# Hexbot_Stm32.net
KiCad netlist of a schematic drawn in Altium Designer
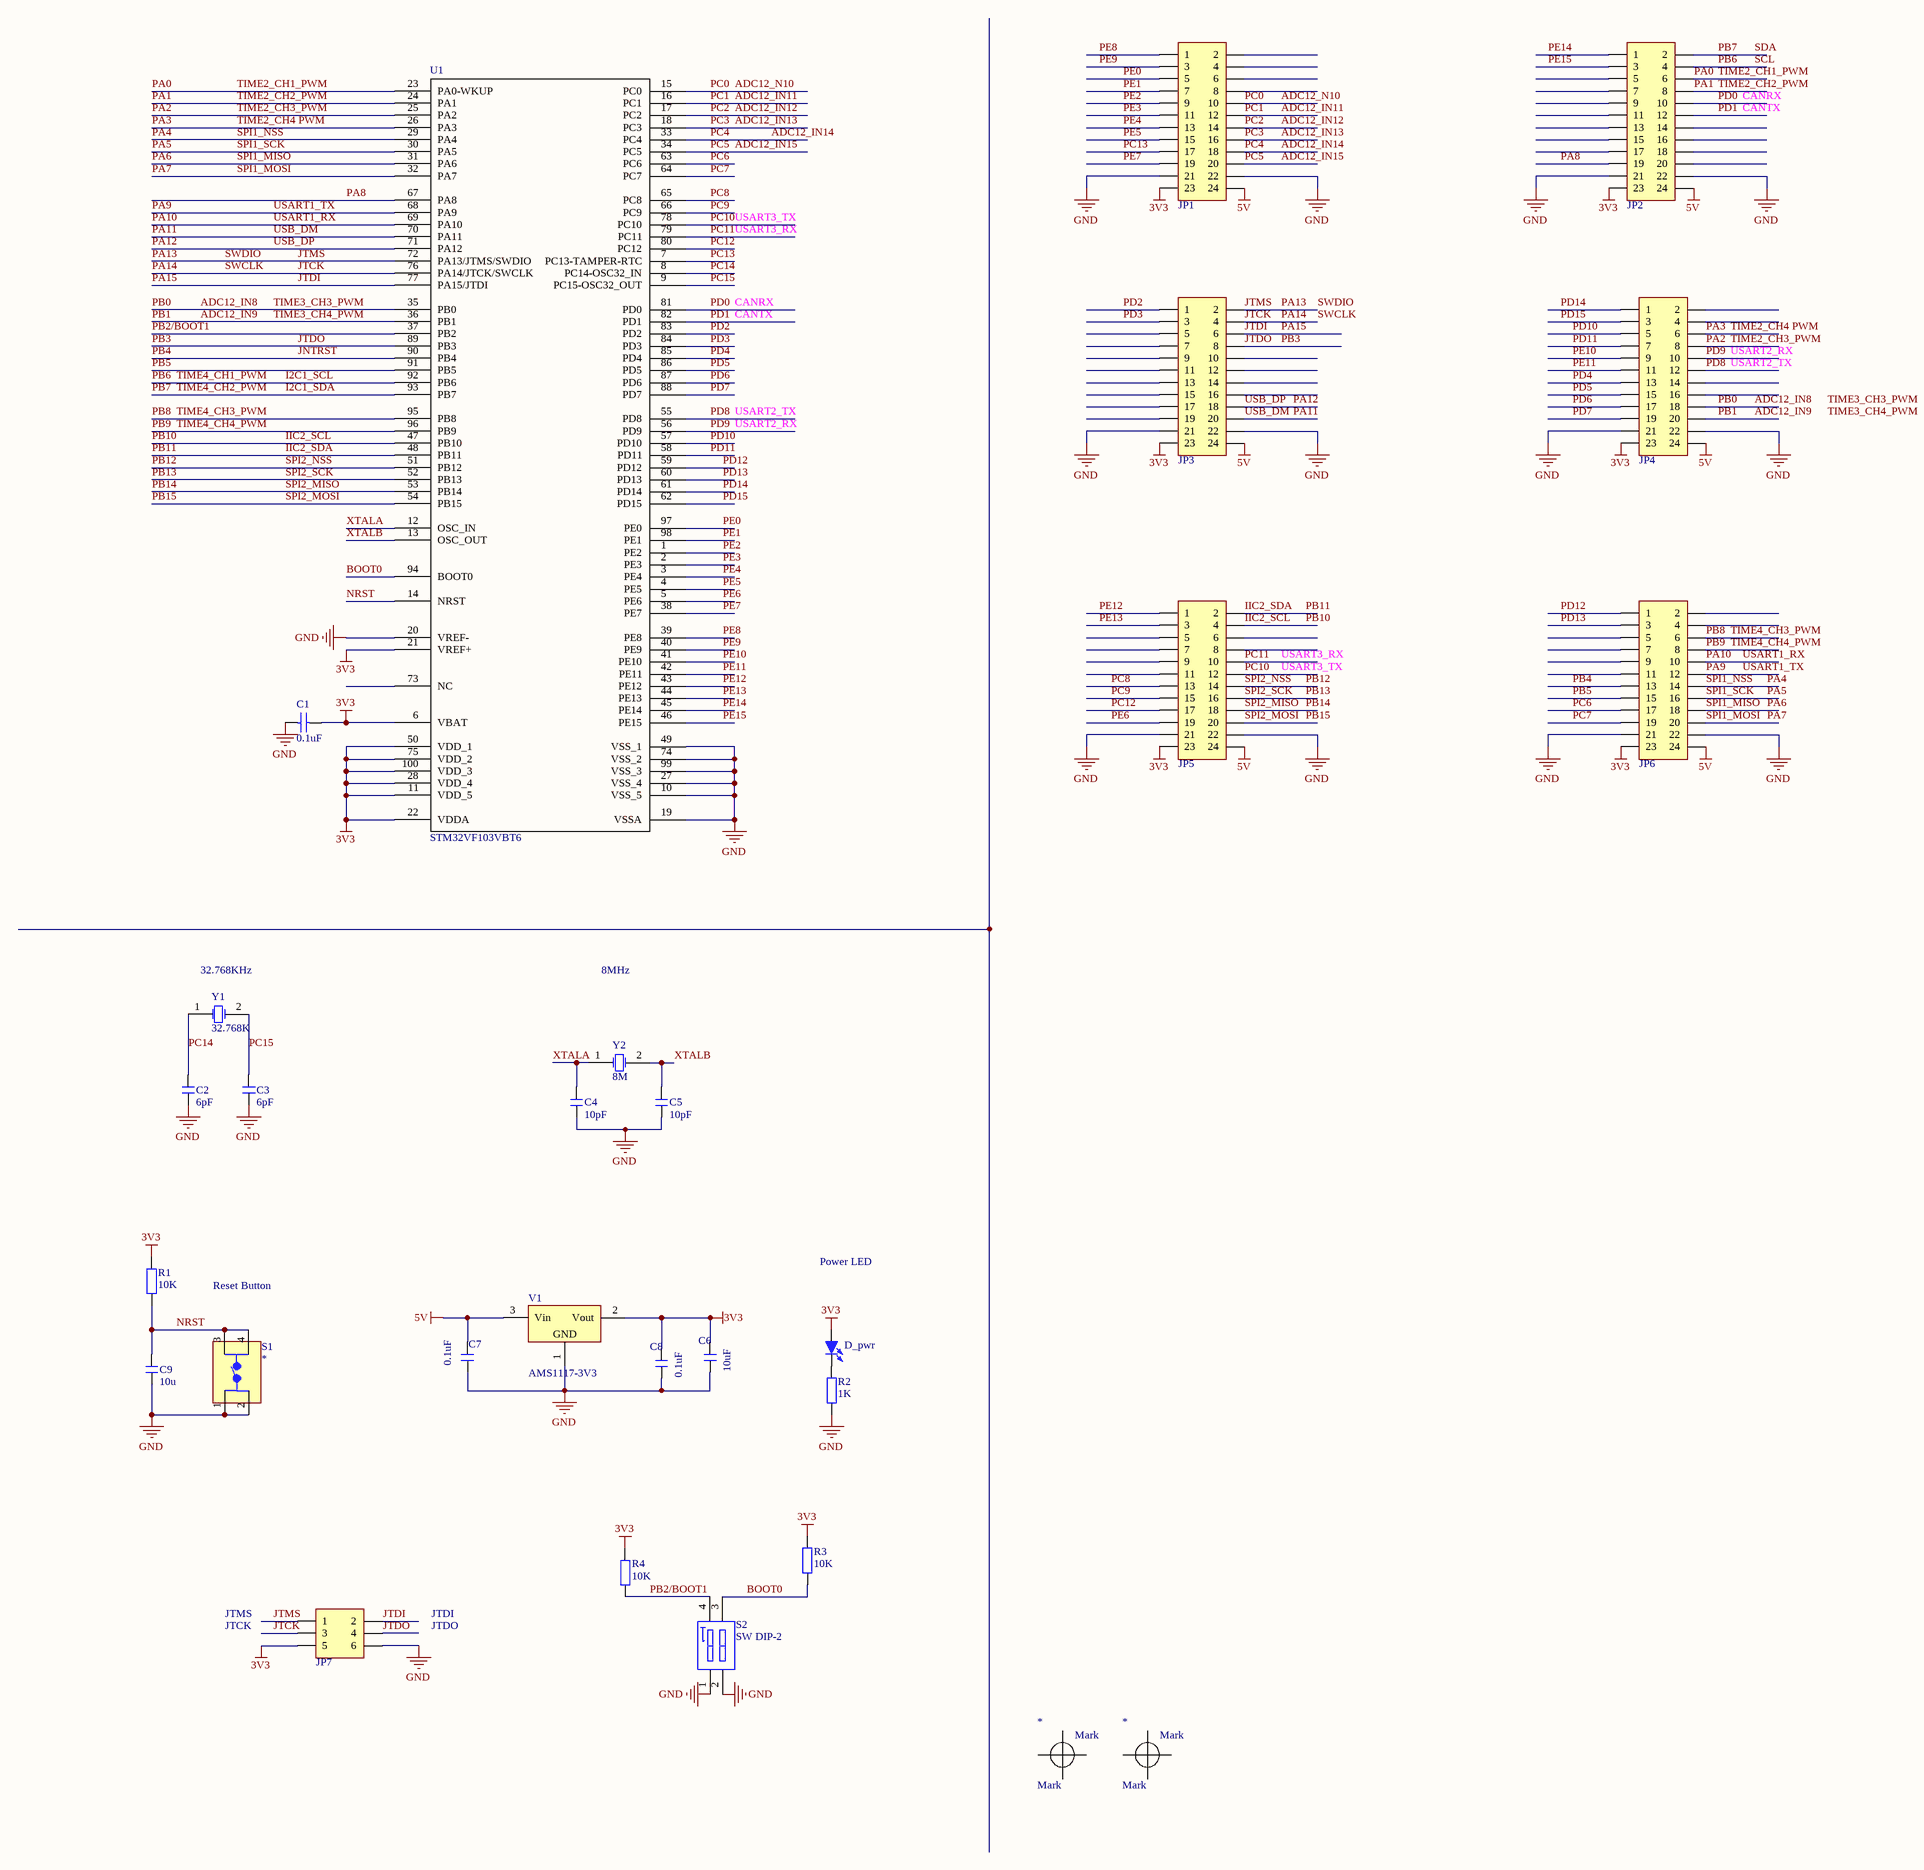
[diagram p0: Hexbot_Stm32.SchDoc]

(export (version "E")
  (design (tool "Eeschema 10.0.6"))
  (components
    (comp (ref "C1")
      (value "0.1uF")
      (footprint "1608[0603]")
      (description "Capacitor (Semiconductor SIM Model)")
      (fields (field (name "Comment") "Cap Semi") (field (name "PUBLISHER") "Altium Limited"))
      (libsource (lib "Miscellaneous Devices") (part "Cap Semi"))
    )
    (comp (ref "C2")
      (value "6pF")
      (footprint "C 0603_L")
      (description "贴片电容")
      (libsource (lib "0.1 - 电阻-电容-电感") (part "C"))
    )
    (comp (ref "C3")
      (value "6pF")
      (footprint "C 0603_L")
      (description "贴片电容")
      (libsource (lib "0.1 - 电阻-电容-电感") (part "C"))
    )
    (comp (ref "C4")
      (value "10pF")
      (footprint "C 0603_L")
      (description "贴片电容")
      (libsource (lib "0.1 - 电阻-电容-电感") (part "C"))
    )
    (comp (ref "C5")
      (value "10pF")
      (footprint "C 0603_L")
      (description "贴片电容")
      (libsource (lib "0.1 - 电阻-电容-电感") (part "C"))
    )
    (comp (ref "C6")
      (value "10uF")
      (footprint "C 0603_L")
      (description "贴片电容")
      (libsource (lib "0.1 - 电阻-电容-电感") (part "C"))
    )
    (comp (ref "C7")
      (value "0.1uF")
      (footprint "C 0603_L")
      (description "贴片电容")
      (libsource (lib "0.1 - 电阻-电容-电感") (part "C"))
    )
    (comp (ref "C8")
      (value "0.1uF")
      (footprint "C 0603_L")
      (description "贴片电容")
      (libsource (lib "0.1 - 电阻-电容-电感") (part "C"))
    )
    (comp (ref "C9")
      (value "10u")
      (footprint "C 0603_L")
      (description "贴片电容")
      (libsource (lib "0.1 - 电阻-电容-电感") (part "C"))
    )
    (comp (ref "D_pwr")
      (value "~")
      (footprint "LED 0603R")
      (description "贴片LED")
      (fields (field (name "版权归属") "封装库来自淘宝 ID：黄晶宝石"))
      (libsource (lib "0.3 - LED发光二极管") (part "LED-SMD"))
    )
    (comp (ref "JP1")
      (value "Header 2X11")
      (footprint "HDR2.54-WI-2x12P")
      (description "12*2P接插件")
      (fields (field (name "版权归属") "封装库来自淘宝卖家 ID：黄晶宝石"))
      (libsource (lib "5.4 - 接插件-脚距2.54 (100mil) ") (part "Header 12X2"))
    )
    (comp (ref "JP2")
      (value "Header 2X11")
      (footprint "HDR2.54-WI-2x12P")
      (description "12*2P接插件")
      (fields (field (name "版权归属") "封装库来自淘宝卖家 ID：黄晶宝石"))
      (libsource (lib "5.4 - 接插件-脚距2.54 (100mil) ") (part "Header 12X2"))
    )
    (comp (ref "JP3")
      (value "Header 2X11")
      (footprint "HDR2.54-WI-2x12P")
      (description "12*2P接插件")
      (fields (field (name "版权归属") "封装库来自淘宝卖家 ID：黄晶宝石"))
      (libsource (lib "5.4 - 接插件-脚距2.54 (100mil) ") (part "Header 12X2"))
    )
    (comp (ref "JP4")
      (value "Header 2X11")
      (footprint "HDR2.54-WI-2x12P")
      (description "12*2P接插件")
      (fields (field (name "版权归属") "封装库来自淘宝卖家 ID：黄晶宝石"))
      (libsource (lib "5.4 - 接插件-脚距2.54 (100mil) ") (part "Header 12X2"))
    )
    (comp (ref "JP5")
      (value "Header 2X11")
      (footprint "HDR2.54-WI-2x12P")
      (description "12*2P接插件")
      (fields (field (name "版权归属") "封装库来自淘宝卖家 ID：黄晶宝石"))
      (libsource (lib "5.4 - 接插件-脚距2.54 (100mil) ") (part "Header 12X2"))
    )
    (comp (ref "JP6")
      (value "Header 2X11")
      (footprint "HDR2.54-WI-2x12P")
      (description "12*2P接插件")
      (fields (field (name "版权归属") "封装库来自淘宝卖家 ID：黄晶宝石"))
      (libsource (lib "5.4 - 接插件-脚距2.54 (100mil) ") (part "Header 12X2"))
    )
    (comp (ref "JP7")
      (value "Header3X2")
      (footprint "HDR2.54-LI-2x3P")
      (description "3*2P接插件")
      (fields (field (name "版权归属") "封装库来自淘宝 ID：黄晶宝石"))
      (libsource (lib "5.4 - 接插件-脚距2.54 (100mil) ") (part "Header 3X2"))
    )
    (comp (ref "R1")
      (value "10K")
      (footprint "R 0603_L")
      (description "贴片电阻")
      (fields (field (name "版权归属") "来自淘宝 ID：黄晶宝石"))
      (libsource (lib "0.1 - 电阻-电容-电感") (part "R"))
    )
    (comp (ref "R2")
      (value "1K")
      (footprint "R 0603_L")
      (description "贴片电阻")
      (fields (field (name "版权归属") "来自淘宝 ID：黄晶宝石"))
      (libsource (lib "0.1 - 电阻-电容-电感") (part "R"))
    )
    (comp (ref "R3")
      (value "10K")
      (footprint "R 0603_L")
      (description "贴片电阻")
      (fields (field (name "版权归属") "来自淘宝 ID：黄晶宝石"))
      (libsource (lib "0.1 - 电阻-电容-电感") (part "R"))
    )
    (comp (ref "R4")
      (value "10K")
      (footprint "R 0603_L")
      (description "贴片电阻")
      (fields (field (name "版权归属") "来自淘宝 ID：黄晶宝石"))
      (libsource (lib "0.1 - 电阻-电容-电感") (part "R"))
    )
    (comp (ref "S1")
      (value "4-1437565-1")
      (footprint "BUTTON")
      (description "Tactile Switch SPST-NO Top Actuated Surface Mount")
      (fields
        (field (name "MP") "FSM4JSMA")
        (field (name "MF") "TE Connectivity")
        (field (name "COMMENT_1") "*")
      )
      (libsource (lib "hexbot_main") (part "FSM4JSMA"))
    )
    (comp (ref "S2")
      (value "SW DIP-2")
      (footprint "SMD-2")
      (description "DIP Switch, 2 Position, SPST")
      (fields (field (name "PUBLISHER") "Altium Limited"))
      (libsource (lib "hexbot_main") (part "SW DIP-2"))
    )
    (comp (ref "U1")
      (value "STM32VF103VBT6")
      (footprint "GDF103C8T6QFN100")
      (libsource (lib "GD32VF103VBT6") (part "GD32VF103VBT6"))
    )
    (comp (ref "V1")
      (value "AMS1117-3V3")
      (footprint "SOT223_L")
      (description "三端稳压芯片")
      (libsource (lib "1.1 - 电源类芯片") (part "AMS1117"))
    )
    (comp (ref "Y1")
      (value "32.768K")
      (footprint "32.768KHZ")
      (description "Crystal Oscillator")
      (fields (field (name "PUBLISHER") "Altium Limited"))
      (libsource (lib "hexbot_main") (part "XTAL_1"))
    )
    (comp (ref "Y2")
      (value "8M")
      (footprint "8M")
      (description "Crystal Oscillator")
      (fields (field (name "PUBLISHER") "Altium Limited"))
      (libsource (lib "hexbot_main") (part "XTAL_1"))
    )
  )
  (nets
    (net (code "1") (name "/ADC12_IN8") (class "Default")
      (node (ref "JP4") (pin "18") (pinfunction "18_18") (pintype "passive"))
      (node (ref "U1") (pin "35") (pinfunction "PB0_35") (pintype "passive"))
    )
    (net (code "2") (name "/ADC12_IN9") (class "Default")
      (node (ref "JP4") (pin "20") (pinfunction "20_20") (pintype "passive"))
      (node (ref "U1") (pin "36") (pinfunction "PB1_36") (pintype "passive"))
    )
    (net (code "3") (name "/ADC12_IN11") (class "Default")
      (node (ref "JP1") (pin "12") (pinfunction "12_12") (pintype "passive"))
      (node (ref "U1") (pin "16") (pinfunction "PC1_16") (pintype "passive"))
    )
    (net (code "4") (name "/ADC12_IN12") (class "Default")
      (node (ref "JP1") (pin "14") (pinfunction "14_14") (pintype "passive"))
      (node (ref "U1") (pin "17") (pinfunction "PC2_17") (pintype "passive"))
    )
    (net (code "5") (name "/ADC12_IN13") (class "Default")
      (node (ref "JP1") (pin "16") (pinfunction "16_16") (pintype "passive"))
      (node (ref "U1") (pin "18") (pinfunction "PC3_18") (pintype "passive"))
    )
    (net (code "6") (name "/ADC12_IN14") (class "Default")
      (node (ref "JP1") (pin "18") (pinfunction "18_18") (pintype "passive"))
      (node (ref "U1") (pin "33") (pinfunction "PC4_33") (pintype "passive"))
    )
    (net (code "7") (name "/ADC12_IN15") (class "Default")
      (node (ref "JP1") (pin "20") (pinfunction "20_20") (pintype "passive"))
      (node (ref "U1") (pin "34") (pinfunction "PC5_34") (pintype "passive"))
    )
    (net (code "8") (name "/ADC12_N10") (class "Default")
      (node (ref "JP1") (pin "10") (pinfunction "10_10") (pintype "passive"))
      (node (ref "U1") (pin "15") (pinfunction "PC0_15") (pintype "passive"))
    )
    (net (code "9") (name "/BOOT0") (class "Default")
      (node (ref "R3") (pin "1") (pinfunction "1_1") (pintype "passive"))
      (node (ref "S2") (pin "3") (pinfunction "B2_3") (pintype "passive"))
      (node (ref "U1") (pin "94") (pinfunction "BOOT0_94") (pintype "passive"))
    )
    (net (code "10") (name "/CANRX") (class "Default")
      (node (ref "JP2") (pin "10") (pinfunction "10_10") (pintype "passive"))
      (node (ref "U1") (pin "81") (pinfunction "PD0_81") (pintype "passive"))
    )
    (net (code "11") (name "/CANTX") (class "Default")
      (node (ref "JP2") (pin "12") (pinfunction "12_12") (pintype "passive"))
      (node (ref "U1") (pin "82") (pinfunction "PD1_82") (pintype "passive"))
    )
    (net (code "12") (name "/I2C1_SCL") (class "Default")
      (node (ref "JP2") (pin "4") (pinfunction "4_4") (pintype "passive"))
      (node (ref "U1") (pin "92") (pinfunction "PB6_92") (pintype "passive"))
    )
    (net (code "13") (name "/I2C1_SDA") (class "Default")
      (node (ref "JP2") (pin "2") (pinfunction "2_2") (pintype "passive"))
      (node (ref "U1") (pin "93") (pinfunction "PB7_93") (pintype "passive"))
    )
    (net (code "14") (name "/IIC2_SCL") (class "Default")
      (node (ref "JP5") (pin "4") (pinfunction "4_4") (pintype "passive"))
      (node (ref "U1") (pin "47") (pinfunction "PB10_47") (pintype "passive"))
    )
    (net (code "15") (name "/IIC2_SDA") (class "Default")
      (node (ref "JP5") (pin "2") (pinfunction "2_2") (pintype "passive"))
      (node (ref "U1") (pin "48") (pinfunction "PB11_48") (pintype "passive"))
    )
    (net (code "16") (name "/JNTRST") (class "Default")
      (node (ref "JP6") (pin "13") (pinfunction "13_13") (pintype "passive"))
      (node (ref "U1") (pin "90") (pinfunction "PB4_90") (pintype "passive"))
    )
    (net (code "17") (name "/JTCK") (class "Default")
      (node (ref "JP3") (pin "4") (pinfunction "4_4") (pintype "passive"))
      (node (ref "JP7") (pin "3") (pinfunction "3_3") (pintype "passive"))
      (node (ref "U1") (pin "76") (pinfunction "PA14/JTCK/SWCLK_76") (pintype "passive"))
    )
    (net (code "18") (name "/JTDI") (class "Default")
      (node (ref "JP3") (pin "6") (pinfunction "6_6") (pintype "passive"))
      (node (ref "JP7") (pin "2") (pinfunction "2_2") (pintype "passive"))
      (node (ref "U1") (pin "77") (pinfunction "PA15/JTDI_77") (pintype "passive"))
    )
    (net (code "19") (name "/JTDO") (class "Default")
      (node (ref "JP3") (pin "8") (pinfunction "8_8") (pintype "passive"))
      (node (ref "JP7") (pin "4") (pinfunction "4_4") (pintype "passive"))
      (node (ref "U1") (pin "89") (pinfunction "PB3_89") (pintype "passive"))
    )
    (net (code "20") (name "/JTMS") (class "Default")
      (node (ref "JP3") (pin "2") (pinfunction "2_2") (pintype "passive"))
      (node (ref "JP7") (pin "1") (pinfunction "1_1") (pintype "passive"))
      (node (ref "U1") (pin "72") (pinfunction "PA13/JTMS/SWDIO_72") (pintype "passive"))
    )
    (net (code "21") (name "/NRST") (class "Default")
      (node (ref "C9") (pin "2") (pinfunction "2_2") (pintype "passive"))
      (node (ref "R1") (pin "1") (pinfunction "1_1") (pintype "passive"))
      (node (ref "S1") (pin "3") (pinfunction "3_3") (pintype "passive"))
      (node (ref "S1") (pin "4") (pinfunction "4_4") (pintype "passive"))
      (node (ref "U1") (pin "14") (pinfunction "NRST_14") (pintype "passive"))
    )
    (net (code "22") (name "/PA0") (class "Default")
      (node (ref "JP2") (pin "6") (pinfunction "6_6") (pintype "passive"))
      (node (ref "U1") (pin "23") (pinfunction "PA0-WKUP_23") (pintype "passive"))
    )
    (net (code "23") (name "/PA1") (class "Default")
      (node (ref "JP2") (pin "8") (pinfunction "8_8") (pintype "passive"))
      (node (ref "U1") (pin "24") (pinfunction "PA1_24") (pintype "passive"))
    )
    (net (code "24") (name "/PA2") (class "Default")
      (node (ref "JP4") (pin "8") (pinfunction "8_8") (pintype "passive"))
      (node (ref "U1") (pin "25") (pinfunction "PA2_25") (pintype "passive"))
    )
    (net (code "25") (name "/PA3") (class "Default")
      (node (ref "JP4") (pin "6") (pinfunction "6_6") (pintype "passive"))
      (node (ref "U1") (pin "26") (pinfunction "PA3_26") (pintype "passive"))
    )
    (net (code "26") (name "/PA4") (class "Default")
      (node (ref "JP6") (pin "14") (pinfunction "14_14") (pintype "passive"))
      (node (ref "U1") (pin "29") (pinfunction "PA4_29") (pintype "passive"))
    )
    (net (code "27") (name "/PA5") (class "Default")
      (node (ref "JP6") (pin "16") (pinfunction "16_16") (pintype "passive"))
      (node (ref "U1") (pin "30") (pinfunction "PA5_30") (pintype "passive"))
    )
    (net (code "28") (name "/PA6") (class "Default")
      (node (ref "JP6") (pin "18") (pinfunction "18_18") (pintype "passive"))
      (node (ref "U1") (pin "31") (pinfunction "PA6_31") (pintype "passive"))
    )
    (net (code "29") (name "/PA7") (class "Default")
      (node (ref "JP6") (pin "20") (pinfunction "20_20") (pintype "passive"))
      (node (ref "U1") (pin "32") (pinfunction "PA7_32") (pintype "passive"))
    )
    (net (code "30") (name "/PA8") (class "Default")
      (node (ref "JP2") (pin "19") (pinfunction "19_19") (pintype "passive"))
      (node (ref "U1") (pin "67") (pinfunction "PA8_67") (pintype "passive"))
    )
    (net (code "31") (name "/PA9") (class "Default")
      (node (ref "JP6") (pin "12") (pinfunction "12_12") (pintype "passive"))
      (node (ref "U1") (pin "68") (pinfunction "PA9_68") (pintype "passive"))
    )
    (net (code "32") (name "/PA10") (class "Default")
      (node (ref "JP6") (pin "10") (pinfunction "10_10") (pintype "passive"))
      (node (ref "U1") (pin "69") (pinfunction "PA10_69") (pintype "passive"))
    )
    (net (code "33") (name "/PA11") (class "Default")
      (node (ref "JP3") (pin "20") (pinfunction "20_20") (pintype "passive"))
      (node (ref "U1") (pin "70") (pinfunction "PA11_70") (pintype "passive"))
    )
    (net (code "34") (name "/PA12") (class "Default")
      (node (ref "JP3") (pin "18") (pinfunction "18_18") (pintype "passive"))
      (node (ref "U1") (pin "71") (pinfunction "PA12_71") (pintype "passive"))
    )
    (net (code "35") (name "/PB2{slash}BOOT1") (class "Default")
      (node (ref "R4") (pin "1") (pinfunction "1_1") (pintype "passive"))
      (node (ref "S2") (pin "4") (pinfunction "B1_4") (pintype "passive"))
      (node (ref "U1") (pin "37") (pinfunction "PB2_37") (pintype "passive"))
    )
    (net (code "36") (name "/PB5") (class "Default")
      (node (ref "JP6") (pin "15") (pinfunction "15_15") (pintype "passive"))
      (node (ref "U1") (pin "91") (pinfunction "PB5_91") (pintype "passive"))
    )
    (net (code "37") (name "/PB8") (class "Default")
      (node (ref "JP6") (pin "6") (pinfunction "6_6") (pintype "passive"))
      (node (ref "U1") (pin "95") (pinfunction "PB8_95") (pintype "passive"))
    )
    (net (code "38") (name "/PB9") (class "Default")
      (node (ref "JP6") (pin "8") (pinfunction "8_8") (pintype "passive"))
      (node (ref "U1") (pin "96") (pinfunction "PB9_96") (pintype "passive"))
    )
    (net (code "39") (name "/PB12") (class "Default")
      (node (ref "JP5") (pin "14") (pinfunction "14_14") (pintype "passive"))
      (node (ref "U1") (pin "51") (pinfunction "PB12_51") (pintype "passive"))
    )
    (net (code "40") (name "/PB13") (class "Default")
      (node (ref "JP5") (pin "16") (pinfunction "16_16") (pintype "passive"))
      (node (ref "U1") (pin "52") (pinfunction "PB13_52") (pintype "passive"))
    )
    (net (code "41") (name "/PB14") (class "Default")
      (node (ref "JP5") (pin "18") (pinfunction "18_18") (pintype "passive"))
      (node (ref "U1") (pin "53") (pinfunction "PB14_53") (pintype "passive"))
    )
    (net (code "42") (name "/PB15") (class "Default")
      (node (ref "JP5") (pin "20") (pinfunction "20_20") (pintype "passive"))
      (node (ref "U1") (pin "54") (pinfunction "PB15_54") (pintype "passive"))
    )
    (net (code "43") (name "/PC6") (class "Default")
      (node (ref "JP6") (pin "17") (pinfunction "17_17") (pintype "passive"))
      (node (ref "U1") (pin "63") (pinfunction "PC6_63") (pintype "passive"))
    )
    (net (code "44") (name "/PC7") (class "Default")
      (node (ref "JP6") (pin "19") (pinfunction "19_19") (pintype "passive"))
      (node (ref "U1") (pin "64") (pinfunction "PC7_64") (pintype "passive"))
    )
    (net (code "45") (name "/PC8") (class "Default")
      (node (ref "JP5") (pin "13") (pinfunction "13_13") (pintype "passive"))
      (node (ref "U1") (pin "65") (pinfunction "PC8_65") (pintype "passive"))
    )
    (net (code "46") (name "/PC9") (class "Default")
      (node (ref "JP5") (pin "15") (pinfunction "15_15") (pintype "passive"))
      (node (ref "U1") (pin "66") (pinfunction "PC9_66") (pintype "passive"))
    )
    (net (code "47") (name "/PC10") (class "Default")
      (node (ref "JP5") (pin "12") (pinfunction "12_12") (pintype "passive"))
      (node (ref "U1") (pin "78") (pinfunction "PC10_78") (pintype "passive"))
    )
    (net (code "48") (name "/PC11") (class "Default")
      (node (ref "JP5") (pin "10") (pinfunction "10_10") (pintype "passive"))
      (node (ref "U1") (pin "79") (pinfunction "PC11_79") (pintype "passive"))
    )
    (net (code "49") (name "/PC12") (class "Default")
      (node (ref "JP5") (pin "17") (pinfunction "17_17") (pintype "passive"))
      (node (ref "U1") (pin "80") (pinfunction "PC12_80") (pintype "passive"))
    )
    (net (code "50") (name "/PC13") (class "Default")
      (node (ref "JP1") (pin "17") (pinfunction "17_17") (pintype "passive"))
      (node (ref "U1") (pin "7") (pinfunction "PC13-TAMPER-RTC_7") (pintype "passive"))
    )
    (net (code "51") (name "/PC14") (class "Default")
      (node (ref "C2") (pin "2") (pinfunction "2_2") (pintype "passive"))
      (node (ref "U1") (pin "8") (pinfunction "PC14-OSC32_IN_8") (pintype "passive"))
      (node (ref "Y1") (pin "1") (pinfunction "OSC1_1") (pintype "passive"))
    )
    (net (code "52") (name "/PC15") (class "Default")
      (node (ref "C3") (pin "2") (pinfunction "2_2") (pintype "passive"))
      (node (ref "U1") (pin "9") (pinfunction "PC15-OSC32_OUT_9") (pintype "passive"))
      (node (ref "Y1") (pin "2") (pinfunction "OSC2_2") (pintype "passive"))
    )
    (net (code "53") (name "/PD2") (class "Default")
      (node (ref "JP3") (pin "1") (pinfunction "1_1") (pintype "passive"))
      (node (ref "U1") (pin "83") (pinfunction "PD2_83") (pintype "passive"))
    )
    (net (code "54") (name "/PD3") (class "Default")
      (node (ref "JP3") (pin "3") (pinfunction "3_3") (pintype "passive"))
      (node (ref "U1") (pin "84") (pinfunction "PD3_84") (pintype "passive"))
    )
    (net (code "55") (name "/PD4") (class "Default")
      (node (ref "JP4") (pin "13") (pinfunction "13_13") (pintype "passive"))
      (node (ref "U1") (pin "85") (pinfunction "PD4_85") (pintype "passive"))
    )
    (net (code "56") (name "/PD5") (class "Default")
      (node (ref "JP4") (pin "15") (pinfunction "15_15") (pintype "passive"))
      (node (ref "U1") (pin "86") (pinfunction "PD5_86") (pintype "passive"))
    )
    (net (code "57") (name "/PD6") (class "Default")
      (node (ref "JP4") (pin "17") (pinfunction "17_17") (pintype "passive"))
      (node (ref "U1") (pin "87") (pinfunction "PD6_87") (pintype "passive"))
    )
    (net (code "58") (name "/PD7") (class "Default")
      (node (ref "JP4") (pin "19") (pinfunction "19_19") (pintype "passive"))
      (node (ref "U1") (pin "88") (pinfunction "PD7_88") (pintype "passive"))
    )
    (net (code "59") (name "/PD8") (class "Default")
      (node (ref "JP4") (pin "12") (pinfunction "12_12") (pintype "passive"))
      (node (ref "U1") (pin "55") (pinfunction "PD8_55") (pintype "passive"))
    )
    (net (code "60") (name "/PD9") (class "Default")
      (node (ref "JP4") (pin "10") (pinfunction "10_10") (pintype "passive"))
      (node (ref "U1") (pin "56") (pinfunction "PD9_56") (pintype "passive"))
    )
    (net (code "61") (name "/PD10") (class "Default")
      (node (ref "JP4") (pin "5") (pinfunction "5_5") (pintype "passive"))
      (node (ref "U1") (pin "57") (pinfunction "PD10_57") (pintype "passive"))
    )
    (net (code "62") (name "/PD11") (class "Default")
      (node (ref "JP4") (pin "7") (pinfunction "7_7") (pintype "passive"))
      (node (ref "U1") (pin "58") (pinfunction "PD11_58") (pintype "passive"))
    )
    (net (code "63") (name "/PD12") (class "Default")
      (node (ref "JP6") (pin "1") (pinfunction "1_1") (pintype "passive"))
      (node (ref "U1") (pin "59") (pinfunction "PD12_59") (pintype "passive"))
    )
    (net (code "64") (name "/PD13") (class "Default")
      (node (ref "JP6") (pin "3") (pinfunction "3_3") (pintype "passive"))
      (node (ref "U1") (pin "60") (pinfunction "PD13_60") (pintype "passive"))
    )
    (net (code "65") (name "/PD14") (class "Default")
      (node (ref "JP4") (pin "1") (pinfunction "1_1") (pintype "passive"))
      (node (ref "U1") (pin "61") (pinfunction "PD14_61") (pintype "passive"))
    )
    (net (code "66") (name "/PD15") (class "Default")
      (node (ref "JP4") (pin "3") (pinfunction "3_3") (pintype "passive"))
      (node (ref "U1") (pin "62") (pinfunction "PD15_62") (pintype "passive"))
    )
    (net (code "67") (name "/PE0") (class "Default")
      (node (ref "JP1") (pin "5") (pinfunction "5_5") (pintype "passive"))
      (node (ref "U1") (pin "97") (pinfunction "PE0_97") (pintype "passive"))
    )
    (net (code "68") (name "/PE1") (class "Default")
      (node (ref "JP1") (pin "7") (pinfunction "7_7") (pintype "passive"))
      (node (ref "U1") (pin "98") (pinfunction "PE1_98") (pintype "passive"))
    )
    (net (code "69") (name "/PE2") (class "Default")
      (node (ref "JP1") (pin "9") (pinfunction "9_9") (pintype "passive"))
      (node (ref "U1") (pin "1") (pinfunction "PE2_1") (pintype "passive"))
    )
    (net (code "70") (name "/PE3") (class "Default")
      (node (ref "JP1") (pin "11") (pinfunction "11_11") (pintype "passive"))
      (node (ref "U1") (pin "2") (pinfunction "PE3_2") (pintype "passive"))
    )
    (net (code "71") (name "/PE4") (class "Default")
      (node (ref "JP1") (pin "13") (pinfunction "13_13") (pintype "passive"))
      (node (ref "U1") (pin "3") (pinfunction "PE4_3") (pintype "passive"))
    )
    (net (code "72") (name "/PE5") (class "Default")
      (node (ref "JP1") (pin "15") (pinfunction "15_15") (pintype "passive"))
      (node (ref "U1") (pin "4") (pinfunction "PE5_4") (pintype "passive"))
    )
    (net (code "73") (name "/PE6") (class "Default")
      (node (ref "JP5") (pin "19") (pinfunction "19_19") (pintype "passive"))
      (node (ref "U1") (pin "5") (pinfunction "PE6_5") (pintype "passive"))
    )
    (net (code "74") (name "/PE7") (class "Default")
      (node (ref "JP1") (pin "19") (pinfunction "19_19") (pintype "passive"))
      (node (ref "U1") (pin "38") (pinfunction "PE7_38") (pintype "passive"))
    )
    (net (code "75") (name "/PE8") (class "Default")
      (node (ref "JP1") (pin "1") (pinfunction "1_1") (pintype "passive"))
      (node (ref "U1") (pin "39") (pinfunction "PE8_39") (pintype "passive"))
    )
    (net (code "76") (name "/PE9") (class "Default")
      (node (ref "JP1") (pin "3") (pinfunction "3_3") (pintype "passive"))
      (node (ref "U1") (pin "40") (pinfunction "PE9_40") (pintype "passive"))
    )
    (net (code "77") (name "/PE10") (class "Default")
      (node (ref "JP4") (pin "9") (pinfunction "9_9") (pintype "passive"))
      (node (ref "U1") (pin "41") (pinfunction "PE10_41") (pintype "passive"))
    )
    (net (code "78") (name "/PE11") (class "Default")
      (node (ref "JP4") (pin "11") (pinfunction "11_11") (pintype "passive"))
      (node (ref "U1") (pin "42") (pinfunction "PE11_42") (pintype "passive"))
    )
    (net (code "79") (name "/PE12") (class "Default")
      (node (ref "JP5") (pin "1") (pinfunction "1_1") (pintype "passive"))
      (node (ref "U1") (pin "43") (pinfunction "PE12_43") (pintype "passive"))
    )
    (net (code "80") (name "/PE13") (class "Default")
      (node (ref "JP5") (pin "3") (pinfunction "3_3") (pintype "passive"))
      (node (ref "U1") (pin "44") (pinfunction "PE13_44") (pintype "passive"))
    )
    (net (code "81") (name "/PE14") (class "Default")
      (node (ref "JP2") (pin "1") (pinfunction "1_1") (pintype "passive"))
      (node (ref "U1") (pin "45") (pinfunction "PE14_45") (pintype "passive"))
    )
    (net (code "82") (name "/PE15") (class "Default")
      (node (ref "JP2") (pin "3") (pinfunction "3_3") (pintype "passive"))
      (node (ref "U1") (pin "46") (pinfunction "PE15_46") (pintype "passive"))
    )
    (net (code "83") (name "/XTALA") (class "Default")
      (node (ref "C4") (pin "2") (pinfunction "2_2") (pintype "passive"))
      (node (ref "U1") (pin "12") (pinfunction "OSC_IN_12") (pintype "passive"))
      (node (ref "Y2") (pin "1") (pinfunction "OSC1_1") (pintype "passive"))
    )
    (net (code "84") (name "/XTALB") (class "Default")
      (node (ref "C5") (pin "2") (pinfunction "2_2") (pintype "passive"))
      (node (ref "U1") (pin "13") (pinfunction "OSC_OUT_13") (pintype "passive"))
      (node (ref "Y2") (pin "2") (pinfunction "OSC2_2") (pintype "passive"))
    )
    (net (code "85") (name "3V3") (class "Default")
      (node (ref "C1") (pin "2") (pinfunction "2_2") (pintype "passive"))
      (node (ref "C6") (pin "2") (pinfunction "2_2") (pintype "passive"))
      (node (ref "C8") (pin "2") (pinfunction "2_2") (pintype "passive"))
      (node (ref "D_pwr") (pin "1") (pinfunction "A_1") (pintype "passive"))
      (node (ref "JP1") (pin "23") (pinfunction "23_23") (pintype "passive"))
      (node (ref "JP2") (pin "23") (pinfunction "23_23") (pintype "passive"))
      (node (ref "JP3") (pin "23") (pinfunction "23_23") (pintype "passive"))
      (node (ref "JP4") (pin "23") (pinfunction "23_23") (pintype "passive"))
      (node (ref "JP5") (pin "23") (pinfunction "23_23") (pintype "passive"))
      (node (ref "JP6") (pin "23") (pinfunction "23_23") (pintype "passive"))
      (node (ref "JP7") (pin "5") (pinfunction "5_5") (pintype "passive"))
      (node (ref "R1") (pin "2") (pinfunction "2_2") (pintype "passive"))
      (node (ref "R3") (pin "2") (pinfunction "2_2") (pintype "passive"))
      (node (ref "R4") (pin "2") (pinfunction "2_2") (pintype "passive"))
      (node (ref "U1") (pin "100") (pinfunction "VDD_3_100") (pintype "passive"))
      (node (ref "U1") (pin "11") (pinfunction "VDD_5_11") (pintype "passive"))
      (node (ref "U1") (pin "21") (pinfunction "VREF+_21") (pintype "passive"))
      (node (ref "U1") (pin "22") (pinfunction "VDDA_22") (pintype "passive"))
      (node (ref "U1") (pin "28") (pinfunction "VDD_4_28") (pintype "passive"))
      (node (ref "U1") (pin "50") (pinfunction "VDD_1_50") (pintype "passive"))
      (node (ref "U1") (pin "6") (pinfunction "VBAT_6") (pintype "passive"))
      (node (ref "U1") (pin "75") (pinfunction "VDD_2_75") (pintype "passive"))
      (node (ref "V1") (pin "2") (pinfunction "Vout_2") (pintype "passive"))
    )
    (net (code "86") (name "5V") (class "Default")
      (node (ref "C7") (pin "2") (pinfunction "2_2") (pintype "passive"))
      (node (ref "JP1") (pin "24") (pinfunction "24_24") (pintype "passive"))
      (node (ref "JP2") (pin "24") (pinfunction "24_24") (pintype "passive"))
      (node (ref "JP3") (pin "24") (pinfunction "24_24") (pintype "passive"))
      (node (ref "JP4") (pin "24") (pinfunction "24_24") (pintype "passive"))
      (node (ref "JP5") (pin "24") (pinfunction "24_24") (pintype "passive"))
      (node (ref "JP6") (pin "24") (pinfunction "24_24") (pintype "passive"))
      (node (ref "V1") (pin "3") (pinfunction "Vin_3") (pintype "passive"))
    )
    (net (code "87") (name "GND") (class "Default")
      (node (ref "C1") (pin "1") (pinfunction "1_1") (pintype "passive"))
      (node (ref "C2") (pin "1") (pinfunction "1_1") (pintype "passive"))
      (node (ref "C3") (pin "1") (pinfunction "1_1") (pintype "passive"))
      (node (ref "C4") (pin "1") (pinfunction "1_1") (pintype "passive"))
      (node (ref "C5") (pin "1") (pinfunction "1_1") (pintype "passive"))
      (node (ref "C6") (pin "1") (pinfunction "1_1") (pintype "passive"))
      (node (ref "C7") (pin "1") (pinfunction "1_1") (pintype "passive"))
      (node (ref "C8") (pin "1") (pinfunction "1_1") (pintype "passive"))
      (node (ref "C9") (pin "1") (pinfunction "1_1") (pintype "passive"))
      (node (ref "JP1") (pin "21") (pinfunction "21_21") (pintype "passive"))
      (node (ref "JP1") (pin "22") (pinfunction "22_22") (pintype "passive"))
      (node (ref "JP2") (pin "21") (pinfunction "21_21") (pintype "passive"))
      (node (ref "JP2") (pin "22") (pinfunction "22_22") (pintype "passive"))
      (node (ref "JP3") (pin "21") (pinfunction "21_21") (pintype "passive"))
      (node (ref "JP3") (pin "22") (pinfunction "22_22") (pintype "passive"))
      (node (ref "JP4") (pin "21") (pinfunction "21_21") (pintype "passive"))
      (node (ref "JP4") (pin "22") (pinfunction "22_22") (pintype "passive"))
      (node (ref "JP5") (pin "21") (pinfunction "21_21") (pintype "passive"))
      (node (ref "JP5") (pin "22") (pinfunction "22_22") (pintype "passive"))
      (node (ref "JP6") (pin "21") (pinfunction "21_21") (pintype "passive"))
      (node (ref "JP6") (pin "22") (pinfunction "22_22") (pintype "passive"))
      (node (ref "JP7") (pin "6") (pinfunction "6_6") (pintype "passive"))
      (node (ref "R2") (pin "1") (pinfunction "1_1") (pintype "passive"))
      (node (ref "S1") (pin "1") (pinfunction "1_1") (pintype "passive"))
      (node (ref "S1") (pin "2") (pinfunction "2_2") (pintype "passive"))
      (node (ref "S2") (pin "1") (pinfunction "A1_1") (pintype "passive"))
      (node (ref "S2") (pin "2") (pinfunction "A2_2") (pintype "passive"))
      (node (ref "U1") (pin "10") (pinfunction "VSS_5_10") (pintype "passive"))
      (node (ref "U1") (pin "19") (pinfunction "VSSA_19") (pintype "passive"))
      (node (ref "U1") (pin "20") (pinfunction "VREF-_20") (pintype "passive"))
      (node (ref "U1") (pin "27") (pinfunction "VSS_4_27") (pintype "passive"))
      (node (ref "U1") (pin "49") (pinfunction "VSS_1_49") (pintype "passive"))
      (node (ref "U1") (pin "74") (pinfunction "VSS_2_74") (pintype "passive"))
      (node (ref "U1") (pin "99") (pinfunction "VSS_3_99") (pintype "passive"))
      (node (ref "V1") (pin "1") (pinfunction "GND_1") (pintype "passive"))
    )
    (net (code "88") (name "Net-(D_pwr-K)") (class "Default")
      (node (ref "D_pwr") (pin "2") (pinfunction "K_2") (pintype "passive"))
      (node (ref "R2") (pin "2") (pinfunction "2_2") (pintype "passive"))
    )
    (net (code "89") (name "unconnected-(JP1-Pad2)") (class "Default")
      (node (ref "JP1") (pin "2") (pinfunction "2_2") (pintype "passive"))
    )
    (net (code "90") (name "unconnected-(JP1-Pad4)") (class "Default")
      (node (ref "JP1") (pin "4") (pinfunction "4_4") (pintype "passive"))
    )
    (net (code "91") (name "unconnected-(JP1-Pad6)") (class "Default")
      (node (ref "JP1") (pin "6") (pinfunction "6_6") (pintype "passive"))
    )
    (net (code "92") (name "unconnected-(JP1-Pad8)") (class "Default")
      (node (ref "JP1") (pin "8") (pinfunction "8_8") (pintype "passive"))
    )
    (net (code "93") (name "unconnected-(JP2-Pad5)") (class "Default")
      (node (ref "JP2") (pin "5") (pinfunction "5_5") (pintype "passive"))
    )
    (net (code "94") (name "unconnected-(JP2-Pad7)") (class "Default")
      (node (ref "JP2") (pin "7") (pinfunction "7_7") (pintype "passive"))
    )
    (net (code "95") (name "unconnected-(JP2-Pad9)") (class "Default")
      (node (ref "JP2") (pin "9") (pinfunction "9_9") (pintype "passive"))
    )
    (net (code "96") (name "unconnected-(JP2-Pad11)") (class "Default")
      (node (ref "JP2") (pin "11") (pinfunction "11_11") (pintype "passive"))
    )
    (net (code "97") (name "unconnected-(JP2-Pad13)") (class "Default")
      (node (ref "JP2") (pin "13") (pinfunction "13_13") (pintype "passive"))
    )
    (net (code "98") (name "unconnected-(JP2-Pad14)") (class "Default")
      (node (ref "JP2") (pin "14") (pinfunction "14_14") (pintype "passive"))
    )
    (net (code "99") (name "unconnected-(JP2-Pad15)") (class "Default")
      (node (ref "JP2") (pin "15") (pinfunction "15_15") (pintype "passive"))
    )
    (net (code "100") (name "unconnected-(JP2-Pad16)") (class "Default")
      (node (ref "JP2") (pin "16") (pinfunction "16_16") (pintype "passive"))
    )
    (net (code "101") (name "unconnected-(JP2-Pad17)") (class "Default")
      (node (ref "JP2") (pin "17") (pinfunction "17_17") (pintype "passive"))
    )
    (net (code "102") (name "unconnected-(JP2-Pad18)") (class "Default")
      (node (ref "JP2") (pin "18") (pinfunction "18_18") (pintype "passive"))
    )
    (net (code "103") (name "unconnected-(JP2-Pad20)") (class "Default")
      (node (ref "JP2") (pin "20") (pinfunction "20_20") (pintype "passive"))
    )
    (net (code "104") (name "unconnected-(JP3-Pad5)") (class "Default")
      (node (ref "JP3") (pin "5") (pinfunction "5_5") (pintype "passive"))
    )
    (net (code "105") (name "unconnected-(JP3-Pad7)") (class "Default")
      (node (ref "JP3") (pin "7") (pinfunction "7_7") (pintype "passive"))
    )
    (net (code "106") (name "unconnected-(JP3-Pad9)") (class "Default")
      (node (ref "JP3") (pin "9") (pinfunction "9_9") (pintype "passive"))
    )
    (net (code "107") (name "unconnected-(JP3-Pad10)") (class "Default")
      (node (ref "JP3") (pin "10") (pinfunction "10_10") (pintype "passive"))
    )
    (net (code "108") (name "unconnected-(JP3-Pad11)") (class "Default")
      (node (ref "JP3") (pin "11") (pinfunction "11_11") (pintype "passive"))
    )
    (net (code "109") (name "unconnected-(JP3-Pad12)") (class "Default")
      (node (ref "JP3") (pin "12") (pinfunction "12_12") (pintype "passive"))
    )
    (net (code "110") (name "unconnected-(JP3-Pad13)") (class "Default")
      (node (ref "JP3") (pin "13") (pinfunction "13_13") (pintype "passive"))
    )
    (net (code "111") (name "unconnected-(JP3-Pad14)") (class "Default")
      (node (ref "JP3") (pin "14") (pinfunction "14_14") (pintype "passive"))
    )
    (net (code "112") (name "unconnected-(JP3-Pad15)") (class "Default")
      (node (ref "JP3") (pin "15") (pinfunction "15_15") (pintype "passive"))
    )
    (net (code "113") (name "unconnected-(JP3-Pad16)") (class "Default")
      (node (ref "JP3") (pin "16") (pinfunction "16_16") (pintype "passive"))
    )
    (net (code "114") (name "unconnected-(JP3-Pad17)") (class "Default")
      (node (ref "JP3") (pin "17") (pinfunction "17_17") (pintype "passive"))
    )
    (net (code "115") (name "unconnected-(JP3-Pad19)") (class "Default")
      (node (ref "JP3") (pin "19") (pinfunction "19_19") (pintype "passive"))
    )
    (net (code "116") (name "unconnected-(JP4-Pad2)") (class "Default")
      (node (ref "JP4") (pin "2") (pinfunction "2_2") (pintype "passive"))
    )
    (net (code "117") (name "unconnected-(JP4-Pad4)") (class "Default")
      (node (ref "JP4") (pin "4") (pinfunction "4_4") (pintype "passive"))
    )
    (net (code "118") (name "unconnected-(JP4-Pad14)") (class "Default")
      (node (ref "JP4") (pin "14") (pinfunction "14_14") (pintype "passive"))
    )
    (net (code "119") (name "unconnected-(JP4-Pad16)") (class "Default")
      (node (ref "JP4") (pin "16") (pinfunction "16_16") (pintype "passive"))
    )
    (net (code "120") (name "unconnected-(JP5-Pad5)") (class "Default")
      (node (ref "JP5") (pin "5") (pinfunction "5_5") (pintype "passive"))
    )
    (net (code "121") (name "unconnected-(JP5-Pad6)") (class "Default")
      (node (ref "JP5") (pin "6") (pinfunction "6_6") (pintype "passive"))
    )
    (net (code "122") (name "unconnected-(JP5-Pad7)") (class "Default")
      (node (ref "JP5") (pin "7") (pinfunction "7_7") (pintype "passive"))
    )
    (net (code "123") (name "unconnected-(JP5-Pad8)") (class "Default")
      (node (ref "JP5") (pin "8") (pinfunction "8_8") (pintype "passive"))
    )
    (net (code "124") (name "unconnected-(JP5-Pad9)") (class "Default")
      (node (ref "JP5") (pin "9") (pinfunction "9_9") (pintype "passive"))
    )
    (net (code "125") (name "unconnected-(JP5-Pad11)") (class "Default")
      (node (ref "JP5") (pin "11") (pinfunction "11_11") (pintype "passive"))
    )
    (net (code "126") (name "unconnected-(JP6-Pad2)") (class "Default")
      (node (ref "JP6") (pin "2") (pinfunction "2_2") (pintype "passive"))
    )
    (net (code "127") (name "unconnected-(JP6-Pad4)") (class "Default")
      (node (ref "JP6") (pin "4") (pinfunction "4_4") (pintype "passive"))
    )
    (net (code "128") (name "unconnected-(JP6-Pad5)") (class "Default")
      (node (ref "JP6") (pin "5") (pinfunction "5_5") (pintype "passive"))
    )
    (net (code "129") (name "unconnected-(JP6-Pad7)") (class "Default")
      (node (ref "JP6") (pin "7") (pinfunction "7_7") (pintype "passive"))
    )
    (net (code "130") (name "unconnected-(JP6-Pad9)") (class "Default")
      (node (ref "JP6") (pin "9") (pinfunction "9_9") (pintype "passive"))
    )
    (net (code "131") (name "unconnected-(JP6-Pad11)") (class "Default")
      (node (ref "JP6") (pin "11") (pinfunction "11_11") (pintype "passive"))
    )
    (net (code "132") (name "unconnected-(U1-NC-Pad73)") (class "Default")
      (node (ref "U1") (pin "73") (pinfunction "NC_73") (pintype "passive"))
    )
  )
)
